# Qwiic_Pi_SHIM.net
KiCad netlist of a schematic drawn in EAGLE
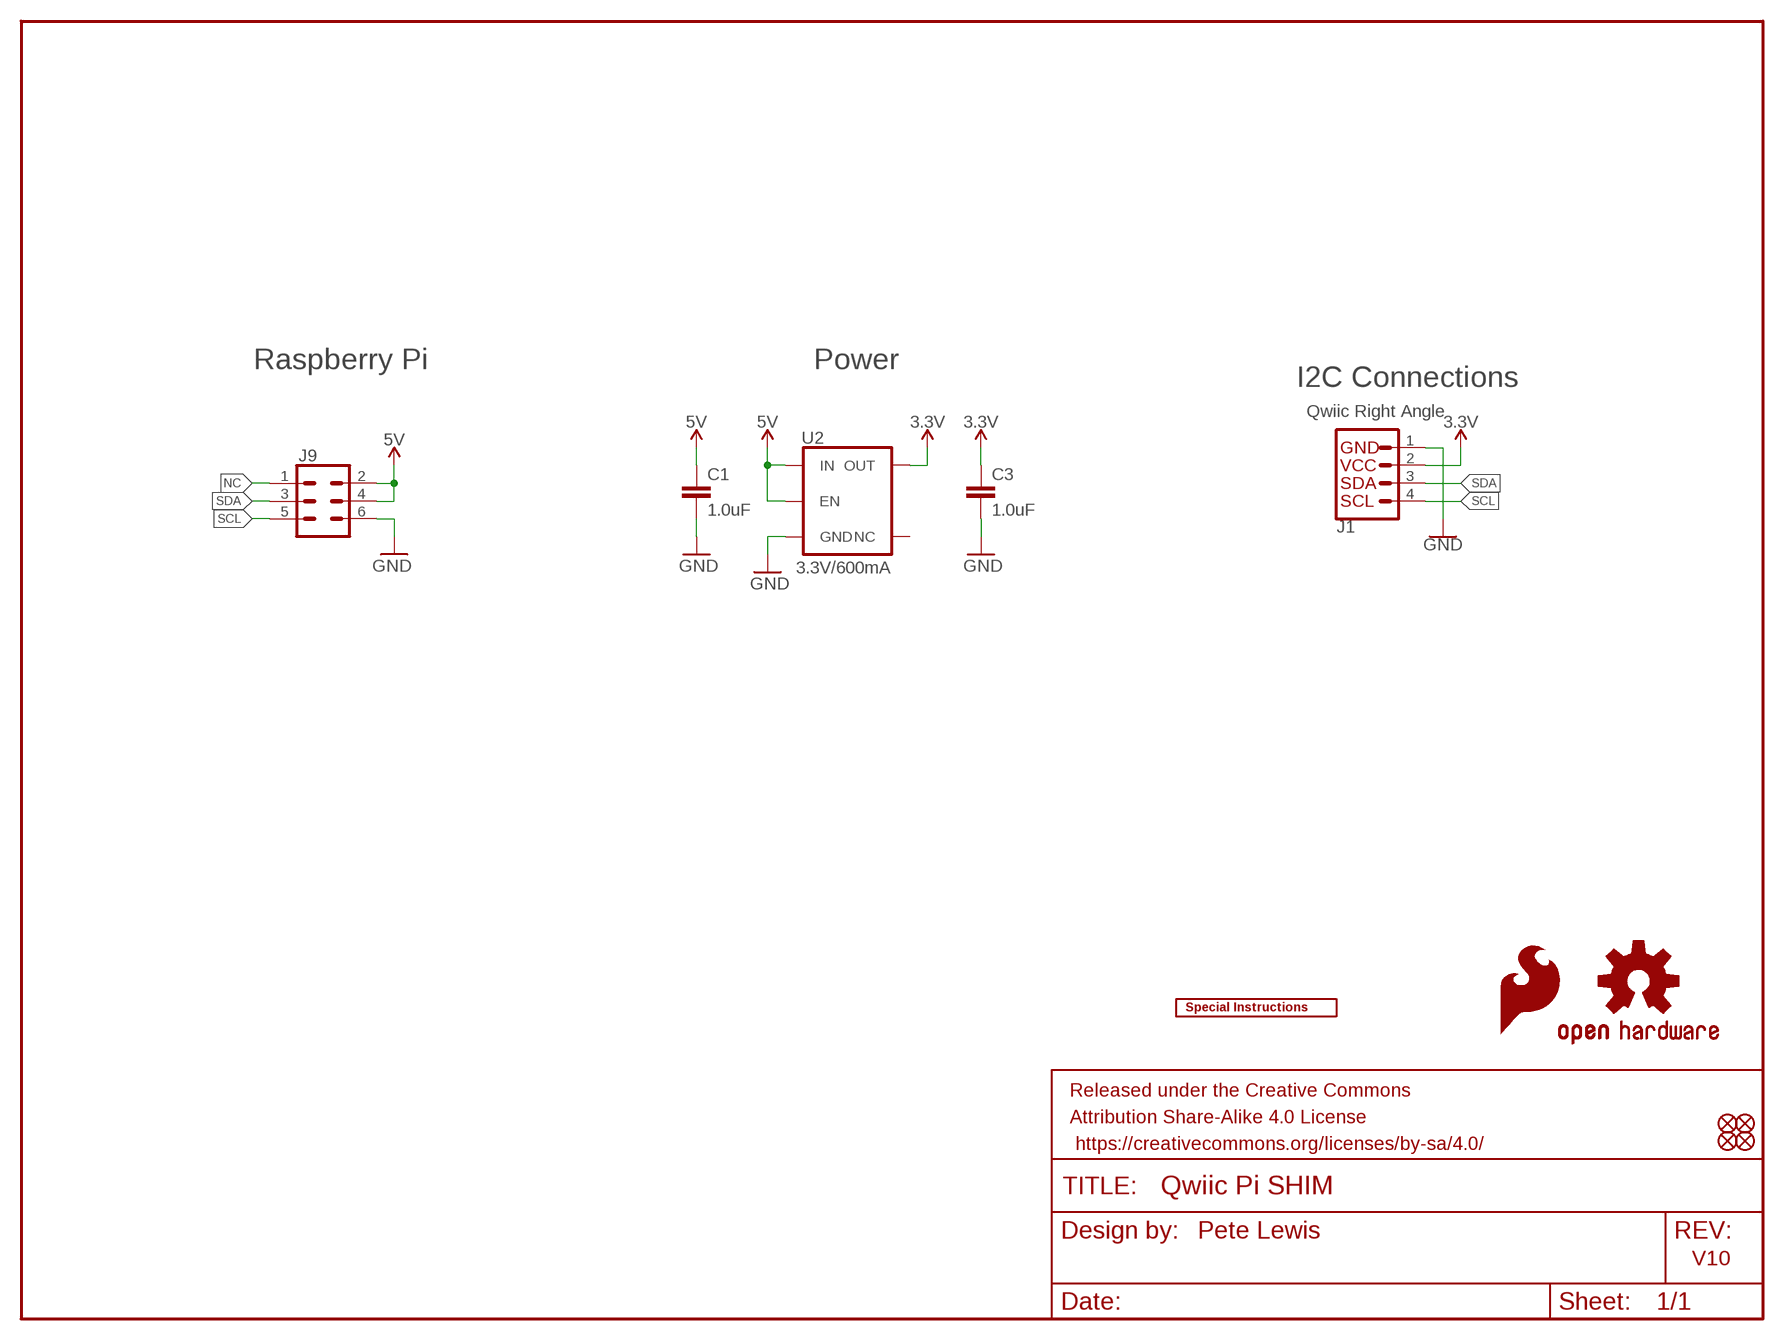
[diagram p0: schematic, sheet 1]

(export (version "E")
  (design (tool "Eeschema 10.0.6"))
  (components
    (comp (ref "C1")
      (value "1.0uF")
      (footprint "eagle-import:0603")
      (libsource (lib "eagle-import") (part "1.0UF-0603-16V-10%"))
    )
    (comp (ref "C3")
      (value "1.0uF")
      (footprint "eagle-import:0603")
      (libsource (lib "eagle-import") (part "1.0UF-0603-16V-10%"))
    )
    (comp (ref "FD1")
      (value "FIDUCIALUFIDUCIAL")
      (footprint "eagle-import:FIDUCIAL-MICRO")
      (libsource (lib "eagle-import") (part "FIDUCIALUFIDUCIAL"))
    )
    (comp (ref "FD2")
      (value "FIDUCIALUFIDUCIAL")
      (footprint "eagle-import:FIDUCIAL-MICRO")
      (libsource (lib "eagle-import") (part "FIDUCIALUFIDUCIAL"))
    )
    (comp (ref "FD3")
      (value "FIDUCIALUFIDUCIAL")
      (footprint "eagle-import:FIDUCIAL-MICRO")
      (libsource (lib "eagle-import") (part "FIDUCIALUFIDUCIAL"))
    )
    (comp (ref "FD4")
      (value "FIDUCIALUFIDUCIAL")
      (footprint "eagle-import:FIDUCIAL-MICRO")
      (libsource (lib "eagle-import") (part "FIDUCIALUFIDUCIAL"))
    )
    (comp (ref "FRAME1")
      (value "FRAME-LETTER")
      (footprint "eagle-import:CREATIVE_COMMONS")
      (libsource (lib "eagle-import") (part "FRAME-LETTER"))
    )
    (comp (ref "J1")
      (value "Qwiic Right Angle")
      (footprint "eagle-import:1X04_1MM_RA")
      (libsource (lib "eagle-import") (part "I2C_STANDARDQWIIC"))
    )
    (comp (ref "J9")
      (value "SPARKFUN-CONNECTORS_CONN_03X2PISHIM_LOCK_SLOTS")
      (footprint "eagle-import:SPARKFUN-CONNECTORS_2X3-NS_PISHIM_LOCKING_SLOTS")
      (libsource (lib "eagle-import") (part "SPARKFUN-CONNECTORS_CONN_03X2PISHIM_LOCK_SLOTS"))
    )
    (comp (ref "LOGO1")
      (value "OSHW-LOGOMINI")
      (footprint "eagle-import:OSHW-LOGO-MINI")
      (libsource (lib "eagle-import") (part "OSHW-LOGOMINI"))
    )
    (comp (ref "U$1")
      (value "SFE_LOGO_FLAME.1_INCH")
      (footprint "eagle-import:SFE_LOGO_FLAME_.1")
      (libsource (lib "eagle-import") (part "SFE_LOGO_FLAME.1_INCH"))
    )
    (comp (ref "U$4")
      (value "SPECIAL_INSTRUCTIONS-ORDERING")
      (footprint "eagle-import:ORDERING_INSTRUCTIONS")
      (libsource (lib "eagle-import") (part "SPECIAL_INSTRUCTIONS-ORDERING"))
    )
    (comp (ref "U2")
      (value "3.3V/600mA")
      (footprint "eagle-import:SOT23-5")
      (libsource (lib "eagle-import") (part "V_REG_AP2112K-3.3V"))
    )
  )
  (nets
    (net (code "1") (name "3.3V") (class "Default")
      (node (ref "C3") (pin "1") (pinfunction "1_1") (pintype "passive"))
      (node (ref "J1") (pin "2") (pinfunction "2_2") (pintype "power_in"))
      (node (ref "U2") (pin "5") (pinfunction "OUT_5") (pintype "passive"))
    )
    (net (code "2") (name "5V") (class "Default")
      (node (ref "C1") (pin "1") (pinfunction "1_1") (pintype "passive"))
      (node (ref "J9") (pin "2") (pinfunction "2_2") (pintype "bidirectional"))
      (node (ref "J9") (pin "4") (pinfunction "4_4") (pintype "bidirectional"))
      (node (ref "U2") (pin "1") (pinfunction "IN_1") (pintype "input"))
      (node (ref "U2") (pin "3") (pinfunction "EN_3") (pintype "input"))
    )
    (net (code "3") (name "GND") (class "Default")
      (node (ref "C1") (pin "2") (pinfunction "2_2") (pintype "passive"))
      (node (ref "C3") (pin "2") (pinfunction "2_2") (pintype "passive"))
      (node (ref "J1") (pin "1") (pinfunction "1_1") (pintype "power_in"))
      (node (ref "J9") (pin "6") (pinfunction "6_6") (pintype "bidirectional"))
      (node (ref "U2") (pin "2") (pinfunction "GND_2") (pintype "input"))
    )
    (net (code "4") (name "NC") (class "Default")
      (node (ref "J9") (pin "1") (pinfunction "1_1") (pintype "bidirectional"))
    )
    (net (code "5") (name "SCL") (class "Default")
      (node (ref "J1") (pin "4") (pinfunction "4_4") (pintype "passive"))
      (node (ref "J9") (pin "5") (pinfunction "5_5") (pintype "bidirectional"))
    )
    (net (code "6") (name "SDA") (class "Default")
      (node (ref "J1") (pin "3") (pinfunction "3_3") (pintype "passive"))
      (node (ref "J9") (pin "3") (pinfunction "3_3") (pintype "bidirectional"))
    )
    (net (code "7") (name "unconnected-(U2-NC-Pad4)") (class "Default")
      (node (ref "U2") (pin "4") (pinfunction "NC_4") (pintype "no_connect"))
    )
  )
)
